# imu_digital.net
KiCad netlist of a schematic drawn in Altium Designer
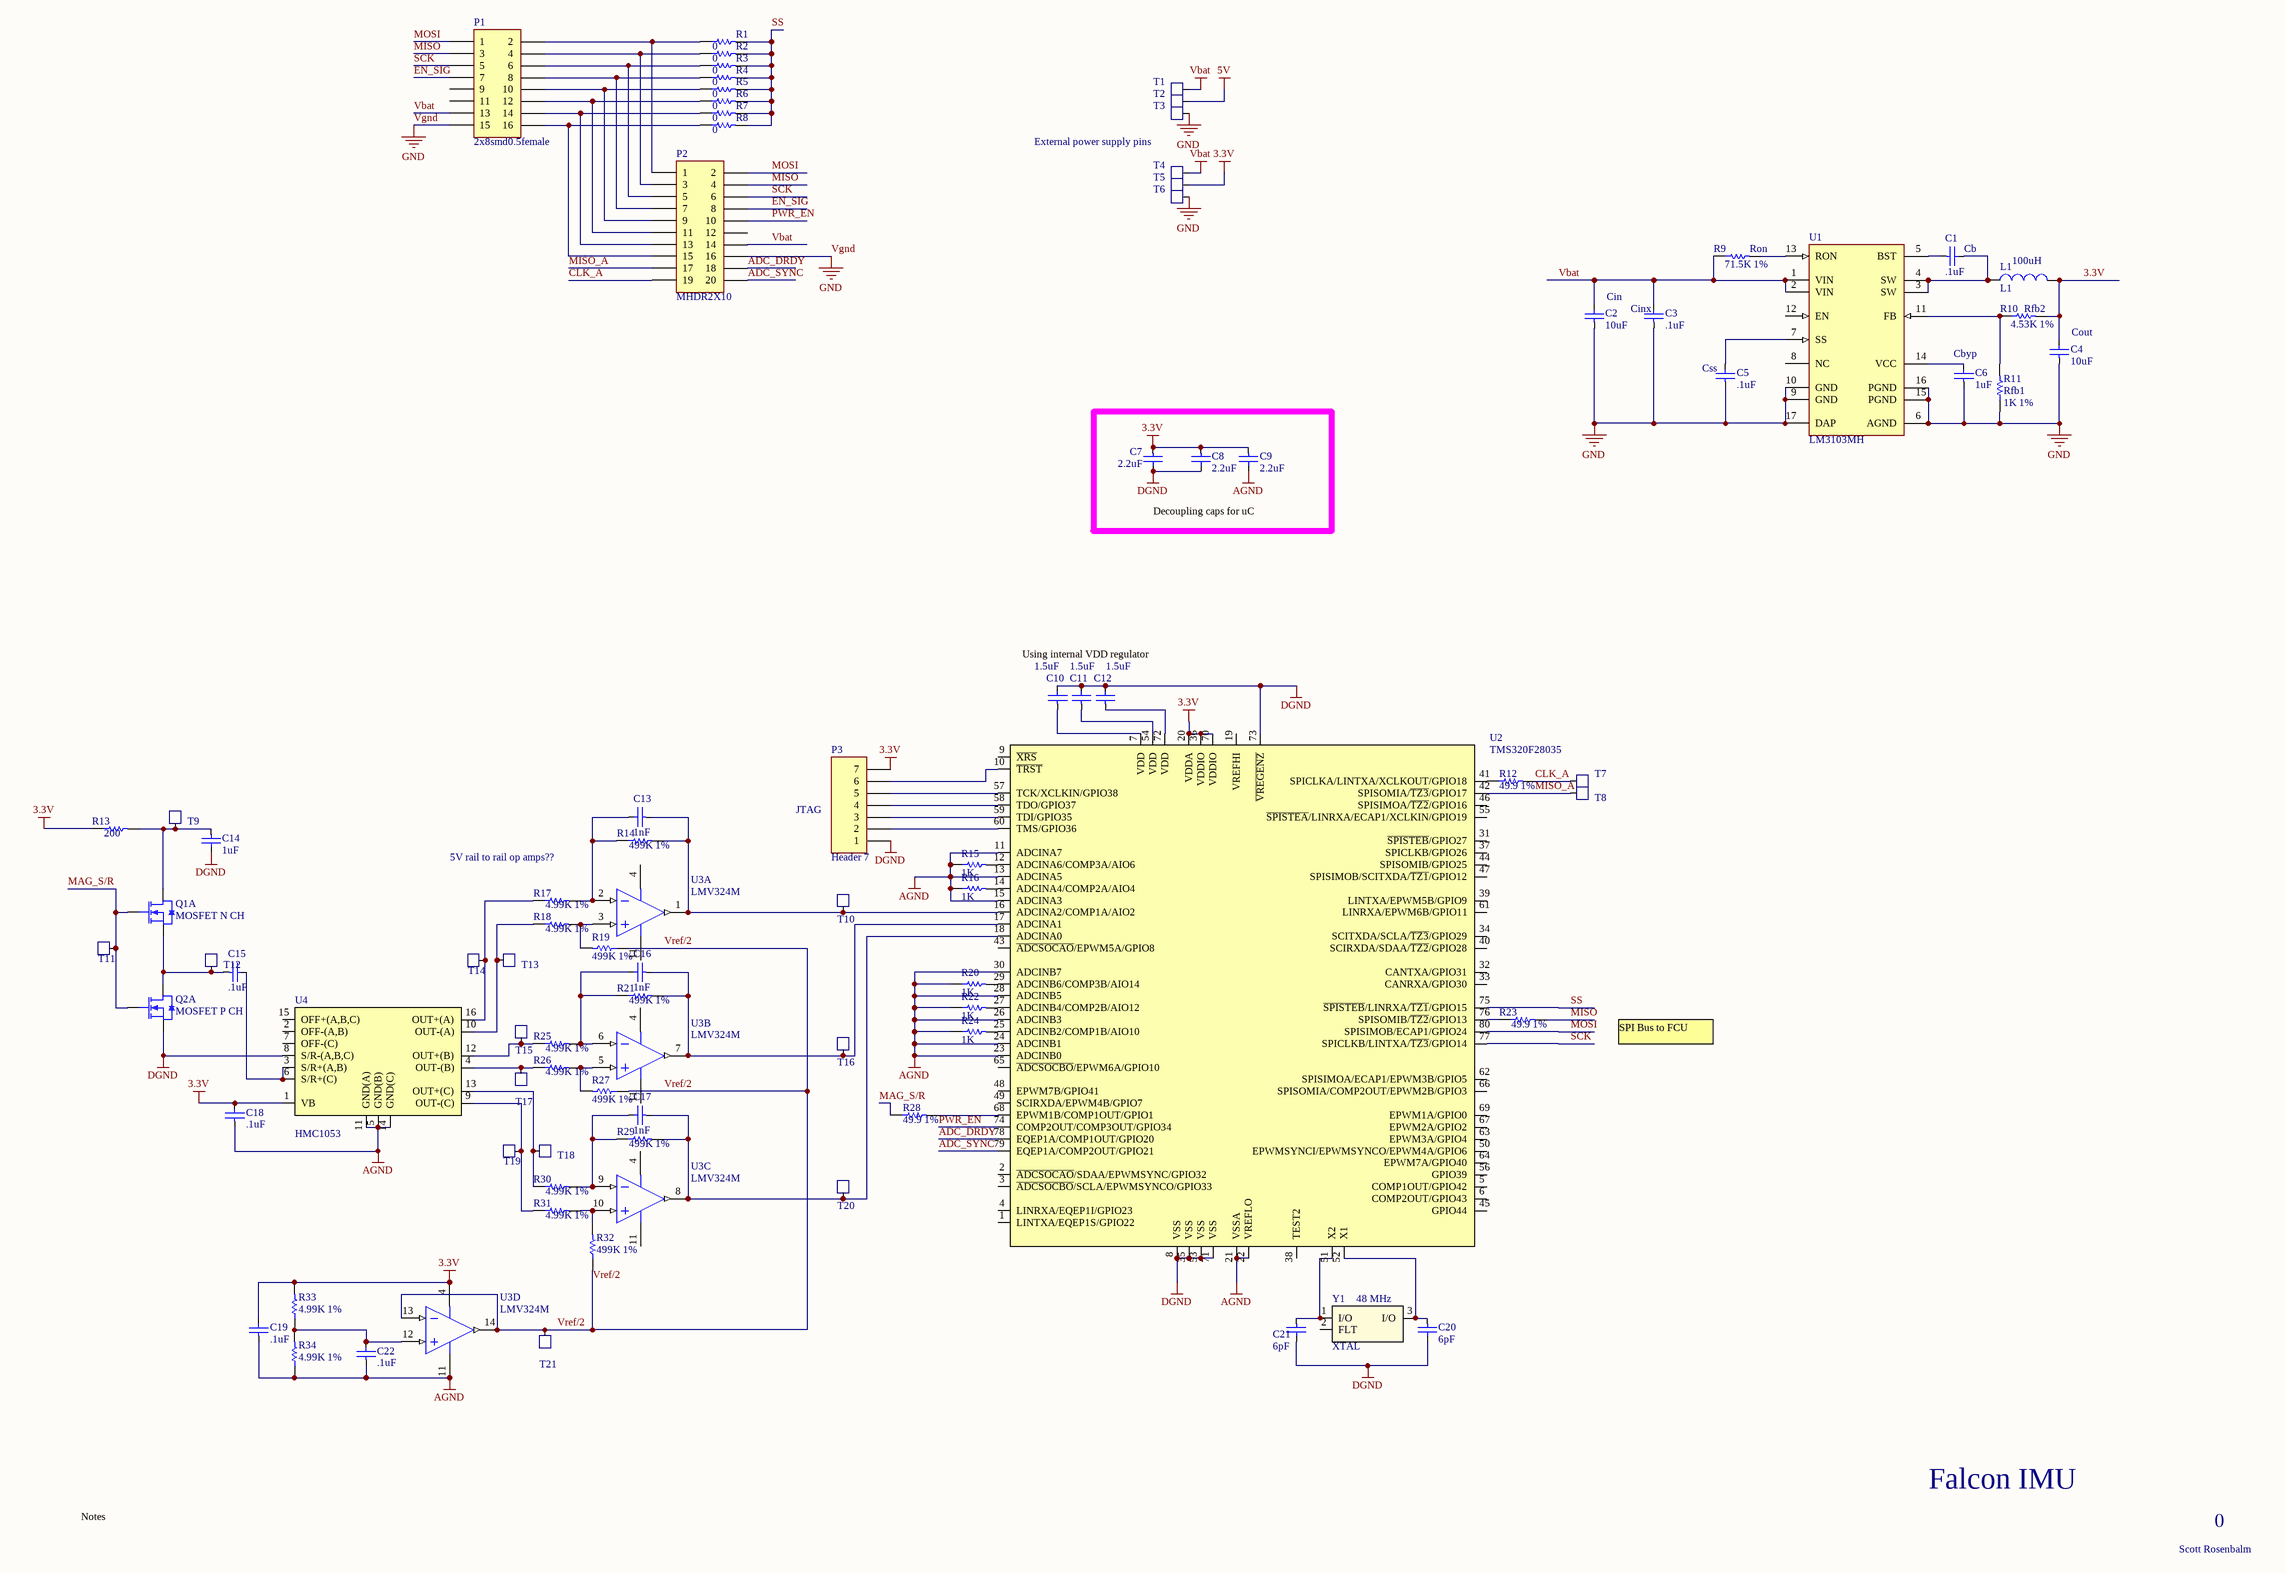
[diagram p0: imu_digital.SchDoc]

(export (version "E")
  (design (tool "Eeschema 10.0.6"))
  (components
    (comp (ref "C1")
      (value "Cb")
      (footprint "0603 (1608)")
      (fields
        (field (name "MANUFACTURER") "Murata")
        (field (name "ALTIUM_VALUE") ".1uF")
        (field (name "PART NO.") "490-1524-1-ND")
      )
      (libsource (lib "SMT Chip") (part "Capacitor"))
    )
    (comp (ref "C2")
      (value "Cin")
      (footprint "1210 (3225)")
      (description "COG Ceramic Cap -> near input to ads1178")
      (fields (field (name "ALTIUM_VALUE") "10uF") (field (name "PART NO.") "810-C3225X7R1E106M"))
      (libsource (lib "SMT Chip") (part "Capacitor"))
    )
    (comp (ref "C3")
      (value "Cinx")
      (footprint "0603 (1608)")
      (fields
        (field (name "MANUFACTURER") "Murata")
        (field (name "ALTIUM_VALUE") ".1uF")
        (field (name "PART NO.") "490-1524-1-ND")
      )
      (libsource (lib "SMT Chip") (part "Capacitor"))
    )
    (comp (ref "C4")
      (value "Cout")
      (footprint "1206 (3216)")
      (description "COG Ceramic Cap -> near input to ads1178")
      (fields (field (name "ALTIUM_VALUE") "10uF") (field (name "PART NO.") "810-C3216X5R1A106M"))
      (libsource (lib "SMT Chip") (part "Capacitor"))
    )
    (comp (ref "C5")
      (value "Css")
      (footprint "0603 (1608)")
      (fields
        (field (name "MANUFACTURER") "Murata")
        (field (name "ALTIUM_VALUE") ".1uF")
        (field (name "PART NO.") "490-1524-1-ND")
      )
      (libsource (lib "SMT Chip") (part "Capacitor"))
    )
    (comp (ref "C6")
      (value "Cbyp")
      (footprint "0603 (1608)")
      (description "COG Ceramic Cap -> near input to ads1178")
      (fields (field (name "ALTIUM_VALUE") "1uF") (field (name "PART NO.") "810-C1608Y5V1A105Z"))
      (libsource (lib "SMT Chip") (part "Capacitor"))
    )
    (comp (ref "C7")
      (value "2.2uF")
      (footprint "0603 (1608)")
      (fields
        (field (name "MANUFACTURER") "TDK")
        (field (name "PART NO.") "445-5167-1-ND")
        (field (name "TOLERANCE") "20%")
      )
      (libsource (lib "SMT Chip") (part "Capacitor"))
    )
    (comp (ref "C8")
      (value "2.2uF")
      (footprint "0603 (1608)")
      (fields
        (field (name "MANUFACTURER") "TDK")
        (field (name "PART NO.") "445-5167-1-ND")
        (field (name "TOLERANCE") "20%")
      )
      (libsource (lib "SMT Chip") (part "Capacitor"))
    )
    (comp (ref "C9")
      (value "2.2uF")
      (footprint "0603 (1608)")
      (fields
        (field (name "MANUFACTURER") "TDK")
        (field (name "PART NO.") "445-5167-1-ND")
        (field (name "TOLERANCE") "20%")
      )
      (libsource (lib "SMT Chip") (part "Capacitor"))
    )
    (comp (ref "C10")
      (value "1.5uF")
      (footprint "0805 (2012)")
      (fields (field (name "MANUFACTURER") "Murata") (field (name "PART NO.") "490-1740-1-ND"))
      (libsource (lib "SMT Chip") (part "Capacitor"))
    )
    (comp (ref "C11")
      (value "1.5uF")
      (footprint "0805 (2012)")
      (fields (field (name "MANUFACTURER") "Murata") (field (name "PART NO.") "490-1740-1-ND"))
      (libsource (lib "SMT Chip") (part "Capacitor"))
    )
    (comp (ref "C12")
      (value "1.5uF")
      (footprint "0805 (2012)")
      (fields (field (name "MANUFACTURER") "Murata") (field (name "PART NO.") "490-1740-1-ND"))
      (libsource (lib "SMT Chip") (part "Capacitor"))
    )
    (comp (ref "C13")
      (value "1nF")
      (footprint "0603 (1608)")
      (fields
        (field (name "MANUFACTURER") "Murata")
        (field (name "PART NO.") "490-1451-1-ND")
        (field (name "TOLERANCE") "5%")
      )
      (libsource (lib "SMT Chip") (part "Capacitor"))
    )
    (comp (ref "C14")
      (value "1uF")
      (footprint "0603 (1608)")
      (fields
        (field (name "MANUFACTURER") "Murata")
        (field (name "PART NO.") "81-GRM188R61E105KA12")
        (field (name "TOLERANCE") "10%")
      )
      (libsource (lib "SMT Chip") (part "Capacitor"))
    )
    (comp (ref "C15")
      (value ".1uF")
      (footprint "0603 (1608)")
      (fields
        (field (name "MANUFACTURER") "Murata")
        (field (name "PART NO.") "490-1524-1-ND")
        (field (name "Comment") "Capacitor")
      )
      (libsource (lib "SMT Chip") (part "Capacitor"))
    )
    (comp (ref "C16")
      (value "1nF")
      (footprint "0603 (1608)")
      (fields
        (field (name "MANUFACTURER") "Murata")
        (field (name "PART NO.") "490-1451-1-ND")
        (field (name "TOLERANCE") "5%")
      )
      (libsource (lib "SMT Chip") (part "Capacitor"))
    )
    (comp (ref "C17")
      (value "1nF")
      (footprint "0603 (1608)")
      (fields
        (field (name "MANUFACTURER") "Murata")
        (field (name "PART NO.") "490-1451-1-ND")
        (field (name "TOLERANCE") "5%")
      )
      (libsource (lib "SMT Chip") (part "Capacitor"))
    )
    (comp (ref "C18")
      (value ".1uF")
      (footprint "0603 (1608)")
      (fields
        (field (name "MANUFACTURER") "Murata")
        (field (name "PART NO.") "490-1524-1-ND")
        (field (name "Comment") "Capacitor")
      )
      (libsource (lib "SMT Chip") (part "Capacitor"))
    )
    (comp (ref "C19")
      (value ".1uF")
      (footprint "0603 (1608)")
      (fields
        (field (name "MANUFACTURER") "Murata")
        (field (name "PART NO.") "490-1524-1-ND")
        (field (name "Comment") "Capacitor")
      )
      (libsource (lib "SMT Chip") (part "Capacitor"))
    )
    (comp (ref "C20")
      (value "6pF")
      (footprint "0603 (1608)")
      (fields
        (field (name "MANUFACTURER") "TDK")
        (field (name "PART NO.") "445-5036-1-ND")
        (field (name "TOLERANCE") ".25pF")
      )
      (libsource (lib "SMT Chip") (part "Capacitor"))
    )
    (comp (ref "C21")
      (value "6pF")
      (footprint "0603 (1608)")
      (fields
        (field (name "MANUFACTURER") "TDK")
        (field (name "PART NO.") "445-5036-1-ND")
        (field (name "TOLERANCE") ".25pF")
      )
      (libsource (lib "SMT Chip") (part "Capacitor"))
    )
    (comp (ref "C22")
      (value ".1uF")
      (footprint "0603 (1608)")
      (fields
        (field (name "MANUFACTURER") "Murata")
        (field (name "PART NO.") "490-1524-1-ND")
        (field (name "Comment") "Capacitor")
      )
      (libsource (lib "SMT Chip") (part "Capacitor"))
    )
    (comp (ref "L1")
      (value "L1")
      (footprint "Inductor Footprint")
      (description "Inductor")
      (fields (field (name "ALTIUM_VALUE") "100uH") (field (name "PART NO.") "SDR0604-101KLCT-ND"))
      (libsource (lib "Miscellaneous Devices") (part "Inductor"))
    )
    (comp (ref "P1")
      (value "2x8smd0.5female")
      (footprint "S9007E-08-ND")
      (fields (field (name "PART NO.") "S9007E-08-ND"))
      (libsource (lib "imu") (part "2x8smd0.5female"))
    )
    (comp (ref "P2")
      (value "MHDR2X10")
      (footprint "S9013E-10-ND")
      (description "Header, 10-Pin, Dual row, Male")
      (fields (field (name "PART NO.") "S9013E-10-ND"))
      (libsource (lib "Miscellaneous Connectors") (part "MHDR2X10"))
    )
    (comp (ref "P3")
      (value "Header 7")
      (footprint "HDR1X7")
      (description "Header, 7-Pin")
      (fields (field (name "PUBLISHER") "Altium Limited"))
      (libsource (lib "Miscellaneous Connectors") (part "Header 7"))
    )
    (comp (ref "Q1")
      (value "MOSFET N CH")
      (footprint "SOT563F")
      (fields (field (name "PART NO.") "SI1035X-T1-E3CT-ND") (field (name "MANUFACTURER") "Vishay Siliconx"))
      (libsource (lib "imu") (part "MOSFETs"))
    )
    (comp (ref "Q2")
      (value "MOSFET P CH")
      (footprint "SOT563F")
      (fields (field (name "PART NO.") "SI1035X-T1-E3CT-ND") (field (name "MANUFACTURER") "Vishay Siliconx"))
      (libsource (lib "imu") (part "MOSFETs"))
    )
    (comp (ref "R1")
      (value "0")
      (footprint "0603 (1608)")
      (description "Resistor")
      (fields (field (name "Comment") "Res1") (field (name "PUBLISHER") "Altium Limited"))
      (libsource (lib "Miscellaneous Devices") (part "Res1"))
    )
    (comp (ref "R2")
      (value "0")
      (footprint "0603 (1608)")
      (description "Resistor")
      (fields (field (name "Comment") "Res1") (field (name "PUBLISHER") "Altium Limited"))
      (libsource (lib "Miscellaneous Devices") (part "Res1"))
    )
    (comp (ref "R3")
      (value "0")
      (footprint "0603 (1608)")
      (description "Resistor")
      (fields (field (name "Comment") "Res1") (field (name "PUBLISHER") "Altium Limited"))
      (libsource (lib "Miscellaneous Devices") (part "Res1"))
    )
    (comp (ref "R4")
      (value "0")
      (footprint "0603 (1608)")
      (description "Resistor")
      (fields (field (name "Comment") "Res1") (field (name "PUBLISHER") "Altium Limited"))
      (libsource (lib "Miscellaneous Devices") (part "Res1"))
    )
    (comp (ref "R5")
      (value "0")
      (footprint "0603 (1608)")
      (description "Resistor")
      (fields (field (name "Comment") "Res1") (field (name "PUBLISHER") "Altium Limited"))
      (libsource (lib "Miscellaneous Devices") (part "Res1"))
    )
    (comp (ref "R6")
      (value "0")
      (footprint "0603 (1608)")
      (description "Resistor")
      (fields (field (name "Comment") "Res1") (field (name "PUBLISHER") "Altium Limited"))
      (libsource (lib "Miscellaneous Devices") (part "Res1"))
    )
    (comp (ref "R7")
      (value "0")
      (footprint "0603 (1608)")
      (description "Resistor")
      (fields (field (name "Comment") "Res1") (field (name "PUBLISHER") "Altium Limited"))
      (libsource (lib "Miscellaneous Devices") (part "Res1"))
    )
    (comp (ref "R8")
      (value "0")
      (footprint "0603 (1608)")
      (description "Resistor")
      (fields (field (name "Comment") "Res1") (field (name "PUBLISHER") "Altium Limited"))
      (libsource (lib "Miscellaneous Devices") (part "Res1"))
    )
    (comp (ref "R9")
      (value "Ron")
      (footprint "0603 (1608)")
      (description "Resistor")
      (fields (field (name "ALTIUM_VALUE") "71.5K 1%") (field (name "PART NO.") "P71.5KHCT-ND"))
      (libsource (lib "Miscellaneous Devices") (part "Res1"))
    )
    (comp (ref "R10")
      (value "Rfb2")
      (footprint "0603 (1608)")
      (description "Resistor")
      (fields (field (name "ALTIUM_VALUE") "4.53K 1%") (field (name "PART NO.") "RMCF0603FT4K53CT-ND"))
      (libsource (lib "Miscellaneous Devices") (part "Res1"))
    )
    (comp (ref "R11")
      (value "Rfb1")
      (footprint "0603 (1608)")
      (description "Resistor")
      (fields (field (name "ALTIUM_VALUE") "1K 1%") (field (name "PART NO.") "P1.00KHCT-ND"))
      (libsource (lib "Miscellaneous Devices") (part "Res1"))
    )
    (comp (ref "R12")
      (value "49.9 1%")
      (footprint "0603 (1608)")
      (description "Resistor")
      (fields (field (name "PART NO.") "P49.9HCT-ND") (field (name "Comment") "931 1%"))
      (libsource (lib "Miscellaneous Devices") (part "Res1"))
    )
    (comp (ref "R13")
      (value "200")
      (footprint "0603 (1608)")
      (description "Resistor")
      (fields (field (name "PART NO.") "P200GCT-ND"))
      (libsource (lib "Miscellaneous Devices") (part "Res1"))
    )
    (comp (ref "R14")
      (value "499K 1%")
      (footprint "0603 (1608)")
      (description "Resistor")
      (fields (field (name "PART NO.") "P499KHCT-ND"))
      (libsource (lib "Miscellaneous Devices") (part "Res1"))
    )
    (comp (ref "R15")
      (value "1K")
      (footprint "0603 (1608)")
      (description "Resistor")
      (fields (field (name "PART NO.") "P1.0KGCT-ND") (field (name "TOLERANCE") "5%"))
      (libsource (lib "Miscellaneous Devices") (part "Res1"))
    )
    (comp (ref "R16")
      (value "1K")
      (footprint "0603 (1608)")
      (description "Resistor")
      (fields (field (name "PART NO.") "P1.0KGCT-ND") (field (name "TOLERANCE") "5%"))
      (libsource (lib "Miscellaneous Devices") (part "Res1"))
    )
    (comp (ref "R17")
      (value "4.99K 1%")
      (footprint "0603 (1608)")
      (description "Resistor")
      (fields (field (name "PART NO.") "P4.99KHCT-ND") (field (name "Comment") "Res1"))
      (libsource (lib "Miscellaneous Devices") (part "Res1"))
    )
    (comp (ref "R18")
      (value "4.99K 1%")
      (footprint "0603 (1608)")
      (description "Resistor")
      (fields (field (name "PART NO.") "P4.99KHCT-ND") (field (name "Comment") "Res1"))
      (libsource (lib "Miscellaneous Devices") (part "Res1"))
    )
    (comp (ref "R19")
      (value "499K 1%")
      (footprint "0603 (1608)")
      (description "Resistor")
      (fields (field (name "PART NO.") "P499KHCT-ND"))
      (libsource (lib "Miscellaneous Devices") (part "Res1"))
    )
    (comp (ref "R20")
      (value "1K")
      (footprint "0603 (1608)")
      (description "Resistor")
      (fields (field (name "PART NO.") "P1.0KGCT-ND") (field (name "TOLERANCE") "5%"))
      (libsource (lib "Miscellaneous Devices") (part "Res1"))
    )
    (comp (ref "R21")
      (value "499K 1%")
      (footprint "0603 (1608)")
      (description "Resistor")
      (fields (field (name "PART NO.") "P499KHCT-ND"))
      (libsource (lib "Miscellaneous Devices") (part "Res1"))
    )
    (comp (ref "R22")
      (value "1K")
      (footprint "0603 (1608)")
      (description "Resistor")
      (fields (field (name "PART NO.") "P1.0KGCT-ND") (field (name "TOLERANCE") "5%"))
      (libsource (lib "Miscellaneous Devices") (part "Res1"))
    )
    (comp (ref "R23")
      (value "49.9 1%")
      (footprint "0603 (1608)")
      (description "Resistor")
      (fields (field (name "PART NO.") "P49.9HCT-ND") (field (name "Comment") "931 1%"))
      (libsource (lib "Miscellaneous Devices") (part "Res1"))
    )
    (comp (ref "R24")
      (value "1K")
      (footprint "0603 (1608)")
      (description "Resistor")
      (fields (field (name "PART NO.") "P1.0KGCT-ND") (field (name "TOLERANCE") "5%"))
      (libsource (lib "Miscellaneous Devices") (part "Res1"))
    )
    (comp (ref "R25")
      (value "4.99K 1%")
      (footprint "0603 (1608)")
      (description "Resistor")
      (fields (field (name "PART NO.") "P4.99KHCT-ND") (field (name "Comment") "Res1"))
      (libsource (lib "Miscellaneous Devices") (part "Res1"))
    )
    (comp (ref "R26")
      (value "4.99K 1%")
      (footprint "0603 (1608)")
      (description "Resistor")
      (fields (field (name "PART NO.") "P4.99KHCT-ND") (field (name "Comment") "Res1"))
      (libsource (lib "Miscellaneous Devices") (part "Res1"))
    )
    (comp (ref "R27")
      (value "499K 1%")
      (footprint "0603 (1608)")
      (description "Resistor")
      (fields (field (name "PART NO.") "P499KHCT-ND"))
      (libsource (lib "Miscellaneous Devices") (part "Res1"))
    )
    (comp (ref "R28")
      (value "49.9 1%")
      (footprint "0603 (1608)")
      (description "Resistor")
      (fields (field (name "PART NO.") "P49.9HCT-ND") (field (name "Comment") "931 1%"))
      (libsource (lib "Miscellaneous Devices") (part "Res1"))
    )
    (comp (ref "R29")
      (value "499K 1%")
      (footprint "0603 (1608)")
      (description "Resistor")
      (fields (field (name "PART NO.") "P499KHCT-ND"))
      (libsource (lib "Miscellaneous Devices") (part "Res1"))
    )
    (comp (ref "R30")
      (value "4.99K 1%")
      (footprint "0603 (1608)")
      (description "Resistor")
      (fields (field (name "PART NO.") "P4.99KHCT-ND") (field (name "Comment") "Res1"))
      (libsource (lib "Miscellaneous Devices") (part "Res1"))
    )
    (comp (ref "R31")
      (value "4.99K 1%")
      (footprint "0603 (1608)")
      (description "Resistor")
      (fields (field (name "PART NO.") "P4.99KHCT-ND") (field (name "Comment") "Res1"))
      (libsource (lib "Miscellaneous Devices") (part "Res1"))
    )
    (comp (ref "R32")
      (value "499K 1%")
      (footprint "0603 (1608)")
      (description "Resistor")
      (fields (field (name "PART NO.") "P499KHCT-ND"))
      (libsource (lib "Miscellaneous Devices") (part "Res1"))
    )
    (comp (ref "R33")
      (value "4.99K 1%")
      (footprint "0603 (1608)")
      (description "Resistor")
      (fields (field (name "PART NO.") "P4.99KHCT-ND") (field (name "Comment") "Res1"))
      (libsource (lib "Miscellaneous Devices") (part "Res1"))
    )
    (comp (ref "R34")
      (value "4.99K 1%")
      (footprint "0603 (1608)")
      (description "Resistor")
      (fields (field (name "PART NO.") "P4.99KHCT-ND") (field (name "Comment") "Res1"))
      (libsource (lib "Miscellaneous Devices") (part "Res1"))
    )
    (comp (ref "T1") (value "TEST_PAD") (footprint "TEST_PAD") (libsource (lib "") (part "TEST_PAD_1")))
    (comp (ref "T2") (value "TEST_PAD") (footprint "TEST_PAD") (libsource (lib "") (part "TEST_PAD_1")))
    (comp (ref "T3") (value "TEST_PAD") (footprint "TEST_PAD") (libsource (lib "") (part "TEST_PAD_1")))
    (comp (ref "T4") (value "TEST_PAD") (footprint "TEST_PAD") (libsource (lib "") (part "TEST_PAD_1")))
    (comp (ref "T5") (value "TEST_PAD") (footprint "TEST_PAD") (libsource (lib "") (part "TEST_PAD_1")))
    (comp (ref "T6") (value "TEST_PAD") (footprint "TEST_PAD") (libsource (lib "") (part "TEST_PAD_1")))
    (comp (ref "T7") (value "~") (footprint "TEST_PAD") (libsource (lib "") (part "TEST_PAD_2")))
    (comp (ref "T8") (value "~") (footprint "TEST_PAD") (libsource (lib "") (part "TEST_PAD_2")))
    (comp (ref "T9") (value "~") (footprint "TEST_PAD") (libsource (lib "imu") (part "TEST_PAD")))
    (comp (ref "T10") (value "~") (footprint "TEST_PAD") (libsource (lib "imu") (part "TEST_PAD")))
    (comp (ref "T11") (value "~") (footprint "TEST_PAD") (libsource (lib "") (part "TEST_PAD_1")))
    (comp (ref "T12") (value "~") (footprint "TEST_PAD") (libsource (lib "imu") (part "TEST_PAD")))
    (comp (ref "T13") (value "~") (footprint "TEST_PAD") (libsource (lib "") (part "TEST_PAD_2")))
    (comp (ref "T14") (value "~") (footprint "TEST_PAD") (libsource (lib "") (part "TEST_PAD_1")))
    (comp (ref "T15") (value "~") (footprint "TEST_PAD") (libsource (lib "imu") (part "TEST_PAD")))
    (comp (ref "T16") (value "~") (footprint "TEST_PAD") (libsource (lib "imu") (part "TEST_PAD")))
    (comp (ref "T17") (value "~") (footprint "TEST_PAD") (libsource (lib "") (part "TEST_PAD_3")))
    (comp (ref "T18") (value "~") (footprint "TEST_PAD") (libsource (lib "") (part "TEST_PAD_2")))
    (comp (ref "T19") (value "~") (footprint "TEST_PAD") (libsource (lib "") (part "TEST_PAD_1")))
    (comp (ref "T20") (value "~") (footprint "TEST_PAD") (libsource (lib "imu") (part "TEST_PAD")))
    (comp (ref "T21") (value "~") (footprint "TEST_PAD") (libsource (lib "") (part "TEST_PAD_3")))
    (comp (ref "U1")
      (value "LM3103MH")
      (footprint "MXA16A_N")
      (description "Synchronous 1MHz 0.75A Step-Down Voltage  Regulator")
      (fields
        (field (name "MANUFACTURER") "National Semiconductor")
        (field (name "DIGIKEYPARTNUMBER") "LM3103MH-ND")
        (field (name "PUBLISHER") "Altium Limited")
      )
      (libsource (lib "NSC Switcher") (part "LM3103MH"))
    )
    (comp (ref "U2")
      (value "TMS320F28035")
      (footprint "TS-PQFP-G80")
      (description "80-pin")
      (fields
        (field (name "MANUFACTURER") "Texas Instruments")
        (field (name "PART NO.") "TMS320F28035PNS-ND")
      )
      (libsource (lib "imu") (part "TMS320F28035 (80-pin)"))
    )
    (comp (ref "U3")
      (value "LMV324M")
      (footprint "M14A_N")
      (description "General Purpose, Low Voltage, Rail-to-Rail Output Operational Amplifiers")
      (fields
        (field (name "MANUFACTURER") "National Semiconductor")
        (field (name "PART NO.") "LMV324MXCT-ND")
        (field (name "DIGIKEYPARTNUMBER") "LMV324MXCT-ND")
        (field (name "PUBLISHER") "Altium Limited")
      )
      (libsource (lib "NSC Amplifier") (part "LMV324M"))
    )
    (comp (ref "U4") (value "HMC1053") (footprint "LCC-16") (libsource (lib "imu") (part "HMC1053")))
    (comp (ref "Y1")
      (value "XTAL")
      (footprint "Murata XTAL")
      (fields (field (name "PART NO.") "490-5588-1-ND") (field (name "FREQUENCY") "48 MHz"))
      (libsource (lib "imu") (part "XTAL"))
    )
  )
  (nets
    (net (code "1") (name "/ADC_DRDY") (class "Default")
      (node (ref "P2") (pin "18") (pinfunction "18_18") (pintype "passive"))
      (node (ref "U2") (pin "78") (pinfunction "EQEP1A/COMP1OUT/GPIO20_78") (pintype "passive"))
    )
    (net (code "2") (name "/ADC_SYNC") (class "Default")
      (node (ref "P2") (pin "20") (pinfunction "20_20") (pintype "passive"))
      (node (ref "U2") (pin "79") (pinfunction "EQEP1A/COMP2OUT/GPIO21_79") (pintype "passive"))
    )
    (net (code "3") (name "/CLK_A") (class "Default")
      (node (ref "P2") (pin "19") (pinfunction "19_19") (pintype "passive"))
      (node (ref "R12") (pin "2") (pinfunction "2_2") (pintype "passive"))
      (node (ref "T7") (pin "0") (pintype "passive"))
    )
    (net (code "4") (name "/EN_SIG") (class "Default")
      (node (ref "P1") (pin "7") (pinfunction "7_7") (pintype "passive"))
      (node (ref "P2") (pin "8") (pinfunction "8_8") (pintype "passive"))
    )
    (net (code "5") (name "/MAG_S{slash}R") (class "Default")
      (node (ref "Q1") (pin "2") (pinfunction "G1_2") (pintype "passive"))
      (node (ref "Q2") (pin "2") (pinfunction "G1_2") (pintype "passive"))
      (node (ref "R28") (pin "1") (pinfunction "1_1") (pintype "passive"))
      (node (ref "T11") (pin "0") (pintype "passive"))
    )
    (net (code "6") (name "/MISO") (class "Default")
      (node (ref "P1") (pin "3") (pinfunction "3_3") (pintype "passive"))
      (node (ref "P2") (pin "4") (pinfunction "4_4") (pintype "passive"))
      (node (ref "R23") (pin "2") (pinfunction "2_2") (pintype "passive"))
    )
    (net (code "7") (name "/MISO_A") (class "Default")
      (node (ref "P2") (pin "17") (pinfunction "17_17") (pintype "passive"))
      (node (ref "T8") (pin "0") (pintype "passive"))
      (node (ref "U2") (pin "42") (pinfunction "SPISOMIA/~{TZ3}/GPIO17_42") (pintype "passive"))
    )
    (net (code "8") (name "/MOSI") (class "Default")
      (node (ref "P1") (pin "1") (pinfunction "1_1") (pintype "passive"))
      (node (ref "P2") (pin "2") (pinfunction "2_2") (pintype "passive"))
      (node (ref "U2") (pin "80") (pinfunction "SPISIMOB/ECAP1/GPIO24_80") (pintype "passive"))
    )
    (net (code "9") (name "/PWR_EN") (class "Default")
      (node (ref "P2") (pin "10") (pinfunction "10_10") (pintype "passive"))
      (node (ref "U2") (pin "74") (pinfunction "COMP2OUT/COMP3OUT/GPIO34_74") (pintype "passive"))
    )
    (net (code "10") (name "/SCK") (class "Default")
      (node (ref "P1") (pin "5") (pinfunction "5_5") (pintype "passive"))
      (node (ref "P2") (pin "6") (pinfunction "6_6") (pintype "passive"))
      (node (ref "U2") (pin "77") (pinfunction "SPICLKB/LINTXA/~{TZ3}/GPIO14_77") (pintype "passive"))
    )
    (net (code "11") (name "/SS") (class "Default")
      (node (ref "R1") (pin "2") (pinfunction "2_2") (pintype "passive"))
      (node (ref "R2") (pin "2") (pinfunction "2_2") (pintype "passive"))
      (node (ref "R3") (pin "2") (pinfunction "2_2") (pintype "passive"))
      (node (ref "R4") (pin "2") (pinfunction "2_2") (pintype "passive"))
      (node (ref "R5") (pin "2") (pinfunction "2_2") (pintype "passive"))
      (node (ref "R6") (pin "2") (pinfunction "2_2") (pintype "passive"))
      (node (ref "R7") (pin "2") (pinfunction "2_2") (pintype "passive"))
      (node (ref "R8") (pin "2") (pinfunction "2_2") (pintype "passive"))
      (node (ref "U2") (pin "75") (pinfunction "~{SPISTEB}/LINRXA/~{TZ1}/GPIO15_75") (pintype "passive"))
    )
    (net (code "12") (name "/Vref{slash}2") (class "Default")
      (node (ref "R19") (pin "1") (pinfunction "1_1") (pintype "passive"))
      (node (ref "R27") (pin "1") (pinfunction "1_1") (pintype "passive"))
      (node (ref "R32") (pin "1") (pinfunction "1_1") (pintype "passive"))
      (node (ref "T21") (pin "0") (pintype "passive"))
      (node (ref "U3") (pin "13") (pinfunction "IND-_13") (pintype "input"))
      (node (ref "U3") (pin "14") (pinfunction "OUTD_14") (pintype "output"))
    )
    (net (code "13") (name "3.3V") (class "Default")
      (node (ref "C18") (pin "1") (pinfunction "1_1") (pintype "passive"))
      (node (ref "C19") (pin "1") (pinfunction "1_1") (pintype "passive"))
      (node (ref "C4") (pin "1") (pinfunction "1_1") (pintype "passive"))
      (node (ref "C7") (pin "2") (pinfunction "2_2") (pintype "passive"))
      (node (ref "C8") (pin "2") (pinfunction "2_2") (pintype "passive"))
      (node (ref "C9") (pin "2") (pinfunction "2_2") (pintype "passive"))
      (node (ref "L1") (pin "2") (pinfunction "2_2") (pintype "passive"))
      (node (ref "P3") (pin "7") (pinfunction "7_7") (pintype "passive"))
      (node (ref "R10") (pin "2") (pinfunction "2_2") (pintype "passive"))
      (node (ref "R13") (pin "1") (pinfunction "1_1") (pintype "passive"))
      (node (ref "R33") (pin "2") (pinfunction "2_2") (pintype "passive"))
      (node (ref "T5") (pin "0") (pintype "passive"))
      (node (ref "U2") (pin "20") (pinfunction "VDDA_20") (pintype "passive"))
      (node (ref "U2") (pin "36") (pinfunction "VDDIO_36") (pintype "passive"))
      (node (ref "U2") (pin "70") (pinfunction "VDDIO_70") (pintype "passive"))
      (node (ref "U3") (pin "4") (pinfunction "V+_4") (pintype "power_in"))
      (node (ref "U4") (pin "1") (pinfunction "VB_1") (pintype "passive"))
    )
    (net (code "14") (name "5V") (class "Default") (node (ref "T2") (pin "0") (pintype "passive")))
    (net (code "15") (name "AGND") (class "Default")
      (node (ref "C18") (pin "2") (pinfunction "2_2") (pintype "passive"))
      (node (ref "C19") (pin "2") (pinfunction "2_2") (pintype "passive"))
      (node (ref "C22") (pin "2") (pinfunction "2_2") (pintype "passive"))
      (node (ref "C9") (pin "1") (pinfunction "1_1") (pintype "passive"))
      (node (ref "R15") (pin "1") (pinfunction "1_1") (pintype "passive"))
      (node (ref "R16") (pin "1") (pinfunction "1_1") (pintype "passive"))
      (node (ref "R20") (pin "1") (pinfunction "1_1") (pintype "passive"))
      (node (ref "R22") (pin "1") (pinfunction "1_1") (pintype "passive"))
      (node (ref "R24") (pin "1") (pinfunction "1_1") (pintype "passive"))
      (node (ref "R34") (pin "1") (pinfunction "1_1") (pintype "passive"))
      (node (ref "U2") (pin "11") (pinfunction "ADCINA7_11") (pintype "passive"))
      (node (ref "U2") (pin "13") (pinfunction "ADCINA5_13") (pintype "passive"))
      (node (ref "U2") (pin "15") (pinfunction "ADCINA3_15") (pintype "passive"))
      (node (ref "U2") (pin "21") (pinfunction "VSSA_21") (pintype "passive"))
      (node (ref "U2") (pin "22") (pinfunction "VREFLO_22") (pintype "passive"))
      (node (ref "U2") (pin "23") (pinfunction "ADCINB0_23") (pintype "passive"))
      (node (ref "U2") (pin "24") (pinfunction "ADCINB1_24") (pintype "passive"))
      (node (ref "U2") (pin "26") (pinfunction "ADCINB3_26") (pintype "passive"))
      (node (ref "U2") (pin "28") (pinfunction "ADCINB5_28") (pintype "passive"))
      (node (ref "U2") (pin "30") (pinfunction "ADCINB7_30") (pintype "passive"))
      (node (ref "U3") (pin "11") (pinfunction "V-_11") (pintype "power_in"))
      (node (ref "U4") (pin "11") (pinfunction "GND(A)_11") (pintype "passive"))
      (node (ref "U4") (pin "14") (pinfunction "GND(C)_14") (pintype "passive"))
      (node (ref "U4") (pin "5") (pinfunction "GND(B)_5") (pintype "passive"))
    )
    (net (code "16") (name "DGND") (class "Default")
      (node (ref "C10") (pin "1") (pinfunction "1_1") (pintype "passive"))
      (node (ref "C11") (pin "1") (pinfunction "1_1") (pintype "passive"))
      (node (ref "C12") (pin "1") (pinfunction "1_1") (pintype "passive"))
      (node (ref "C14") (pin "1") (pinfunction "1_1") (pintype "passive"))
      (node (ref "C20") (pin "1") (pinfunction "1_1") (pintype "passive"))
      (node (ref "C21") (pin "1") (pinfunction "1_1") (pintype "passive"))
      (node (ref "C7") (pin "1") (pinfunction "1_1") (pintype "passive"))
      (node (ref "C8") (pin "1") (pinfunction "1_1") (pintype "passive"))
      (node (ref "P3") (pin "1") (pinfunction "1_1") (pintype "passive"))
      (node (ref "Q2") (pin "1") (pinfunction "S1_1") (pintype "passive"))
      (node (ref "U2") (pin "35") (pinfunction "VSS_35") (pintype "passive"))
      (node (ref "U2") (pin "53") (pinfunction "VSS_53") (pintype "passive"))
      (node (ref "U2") (pin "71") (pinfunction "VSS_71") (pintype "passive"))
      (node (ref "U2") (pin "73") (pinfunction "~{VREGENZ}_73") (pintype "passive"))
      (node (ref "U2") (pin "8") (pinfunction "VSS_8") (pintype "passive"))
      (node (ref "U4") (pin "8") (pinfunction "S/R-(A,B,C)_8") (pintype "passive"))
    )
    (net (code "17") (name "GND") (class "Default")
      (node (ref "C2") (pin "2") (pinfunction "2_2") (pintype "passive"))
      (node (ref "C3") (pin "2") (pinfunction "2_2") (pintype "passive"))
      (node (ref "C4") (pin "2") (pinfunction "2_2") (pintype "passive"))
      (node (ref "C5") (pin "2") (pinfunction "2_2") (pintype "passive"))
      (node (ref "C6") (pin "2") (pinfunction "2_2") (pintype "passive"))
      (node (ref "P1") (pin "15") (pinfunction "15_15") (pintype "passive"))
      (node (ref "P2") (pin "16") (pinfunction "16_16") (pintype "passive"))
      (node (ref "R11") (pin "1") (pinfunction "1_1") (pintype "passive"))
      (node (ref "T3") (pin "0") (pintype "passive"))
      (node (ref "T6") (pin "0") (pintype "passive"))
      (node (ref "U1") (pin "10") (pinfunction "GND_10") (pintype "power_in"))
      (node (ref "U1") (pin "15") (pinfunction "PGND_15") (pintype "power_in"))
      (node (ref "U1") (pin "16") (pinfunction "PGND_16") (pintype "power_in"))
      (node (ref "U1") (pin "17") (pinfunction "DAP_17") (pintype "power_in"))
      (node (ref "U1") (pin "6") (pinfunction "AGND_6") (pintype "power_in"))
      (node (ref "U1") (pin "9") (pinfunction "GND_9") (pintype "power_in"))
    )
    (net (code "18") (name "Net-(C1-Pad1)") (class "Default")
      (node (ref "C1") (pin "1") (pinfunction "1_1") (pintype "passive"))
      (node (ref "L1") (pin "1") (pinfunction "1_1") (pintype "passive"))
      (node (ref "U1") (pin "3") (pinfunction "SW_3") (pintype "power_in"))
      (node (ref "U1") (pin "4") (pinfunction "SW_4") (pintype "power_in"))
    )
    (net (code "19") (name "Net-(C10-Pad2)") (class "Default")
      (node (ref "C10") (pin "2") (pinfunction "2_2") (pintype "passive"))
      (node (ref "U2") (pin "7") (pinfunction "VDD_7") (pintype "passive"))
    )
    (net (code "20") (name "Net-(C11-Pad2)") (class "Default")
      (node (ref "C11") (pin "2") (pinfunction "2_2") (pintype "passive"))
      (node (ref "U2") (pin "54") (pinfunction "VDD_54") (pintype "passive"))
    )
    (net (code "21") (name "Net-(C12-Pad2)") (class "Default")
      (node (ref "C12") (pin "2") (pinfunction "2_2") (pintype "passive"))
      (node (ref "U2") (pin "72") (pinfunction "VDD_72") (pintype "passive"))
    )
    (net (code "22") (name "Net-(P1-Pad2)") (class "Default")
      (node (ref "P1") (pin "2") (pinfunction "2_2") (pintype "passive"))
      (node (ref "P2") (pin "1") (pinfunction "1_1") (pintype "passive"))
      (node (ref "R1") (pin "1") (pinfunction "1_1") (pintype "passive"))
    )
    (net (code "23") (name "Net-(P1-Pad4)") (class "Default")
      (node (ref "P1") (pin "4") (pinfunction "4_4") (pintype "passive"))
      (node (ref "P2") (pin "3") (pinfunction "3_3") (pintype "passive"))
      (node (ref "R2") (pin "1") (pinfunction "1_1") (pintype "passive"))
    )
    (net (code "24") (name "Net-(P1-Pad6)") (class "Default")
      (node (ref "P1") (pin "6") (pinfunction "6_6") (pintype "passive"))
      (node (ref "P2") (pin "5") (pinfunction "5_5") (pintype "passive"))
      (node (ref "R3") (pin "1") (pinfunction "1_1") (pintype "passive"))
    )
    (net (code "25") (name "Net-(P1-Pad8)") (class "Default")
      (node (ref "P1") (pin "8") (pinfunction "8_8") (pintype "passive"))
      (node (ref "P2") (pin "7") (pinfunction "7_7") (pintype "passive"))
      (node (ref "R4") (pin "1") (pinfunction "1_1") (pintype "passive"))
    )
    (net (code "26") (name "Net-(P1-Pad10)") (class "Default")
      (node (ref "P1") (pin "10") (pinfunction "10_10") (pintype "passive"))
      (node (ref "P2") (pin "9") (pinfunction "9_9") (pintype "passive"))
      (node (ref "R5") (pin "1") (pinfunction "1_1") (pintype "passive"))
    )
    (net (code "27") (name "Net-(P1-Pad12)") (class "Default")
      (node (ref "P1") (pin "12") (pinfunction "12_12") (pintype "passive"))
      (node (ref "P2") (pin "11") (pinfunction "11_11") (pintype "passive"))
      (node (ref "R6") (pin "1") (pinfunction "1_1") (pintype "passive"))
    )
    (net (code "28") (name "Net-(P1-Pad14)") (class "Default")
      (node (ref "P1") (pin "14") (pinfunction "14_14") (pintype "passive"))
      (node (ref "P2") (pin "13") (pinfunction "13_13") (pintype "passive"))
      (node (ref "R7") (pin "1") (pinfunction "1_1") (pintype "passive"))
    )
    (net (code "29") (name "Net-(P1-Pad16)") (class "Default")
      (node (ref "P1") (pin "16") (pinfunction "16_16") (pintype "passive"))
      (node (ref "P2") (pin "15") (pinfunction "15_15") (pintype "passive"))
      (node (ref "R8") (pin "1") (pinfunction "1_1") (pintype "passive"))
    )
    (net (code "30") (name "Net-(Q1A-D1)") (class "Default")
      (node (ref "C14") (pin "2") (pinfunction "2_2") (pintype "passive"))
      (node (ref "Q1") (pin "6") (pinfunction "D1_6") (pintype "passive"))
      (node (ref "R13") (pin "2") (pinfunction "2_2") (pintype "passive"))
      (node (ref "T9") (pin "0") (pintype "passive"))
    )
    (net (code "31") (name "Net-(Q1A-S1)") (class "Default")
      (node (ref "C15") (pin "2") (pinfunction "2_2") (pintype "passive"))
      (node (ref "Q1") (pin "1") (pinfunction "S1_1") (pintype "passive"))
      (node (ref "Q2") (pin "6") (pinfunction "D1_6") (pintype "passive"))
      (node (ref "T12") (pin "0") (pintype "passive"))
    )
    (net (code "32") (name "Net-(U1-BST)") (class "Default")
      (node (ref "C1") (pin "2") (pinfunction "2_2") (pintype "passive"))
      (node (ref "U1") (pin "5") (pinfunction "BST_5") (pintype "passive"))
    )
    (net (code "33") (name "Net-(U1-FB)") (class "Default")
      (node (ref "R10") (pin "1") (pinfunction "1_1") (pintype "passive"))
      (node (ref "R11") (pin "2") (pinfunction "2_2") (pintype "passive"))
      (node (ref "U1") (pin "11") (pinfunction "FB_11") (pintype "input"))
    )
    (net (code "34") (name "Net-(U1-RON)") (class "Default")
      (node (ref "R9") (pin "2") (pinfunction "2_2") (pintype "passive"))
      (node (ref "U1") (pin "13") (pinfunction "RON_13") (pintype "input"))
    )
    (net (code "35") (name "Net-(U1-SS)") (class "Default")
      (node (ref "C5") (pin "1") (pinfunction "1_1") (pintype "passive"))
      (node (ref "U1") (pin "7") (pinfunction "SS_7") (pintype "input"))
    )
    (net (code "36") (name "Net-(U1-VCC)") (class "Default")
      (node (ref "C6") (pin "1") (pinfunction "1_1") (pintype "passive"))
      (node (ref "U1") (pin "14") (pinfunction "VCC_14") (pintype "power_in"))
    )
    (net (code "37") (name "Net-(U2-ADCINA0)") (class "Default")
      (node (ref "C17") (pin "2") (pinfunction "2_2") (pintype "passive"))
      (node (ref "R29") (pin "2") (pinfunction "2_2") (pintype "passive"))
      (node (ref "T20") (pin "0") (pintype "passive"))
      (node (ref "U2") (pin "18") (pinfunction "ADCINA0_18") (pintype "passive"))
      (node (ref "U3") (pin "8") (pinfunction "OUTC_8") (pintype "output"))
    )
    (net (code "38") (name "Net-(U2-ADCINA1)") (class "Default")
      (node (ref "C16") (pin "2") (pinfunction "2_2") (pintype "passive"))
      (node (ref "R21") (pin "2") (pinfunction "2_2") (pintype "passive"))
      (node (ref "T16") (pin "0") (pintype "passive"))
      (node (ref "U2") (pin "17") (pinfunction "ADCINA1_17") (pintype "passive"))
      (node (ref "U3") (pin "7") (pinfunction "OUTB_7") (pintype "output"))
    )
    (net (code "39") (name "Net-(U2-ADCINA2{slash}COMP1A{slash}AIO2)") (class "Default")
      (node (ref "C13") (pin "2") (pinfunction "2_2") (pintype "passive"))
      (node (ref "R14") (pin "2") (pinfunction "2_2") (pintype "passive"))
      (node (ref "T10") (pin "0") (pintype "passive"))
      (node (ref "U2") (pin "16") (pinfunction "ADCINA2/COMP1A/AIO2_16") (pintype "passive"))
      (node (ref "U3") (pin "1") (pinfunction "OUTA_1") (pintype "output"))
    )
    (net (code "40") (name "Net-(U2-ADCINA4{slash}COMP2A{slash}AIO4)") (class "Default")
      (node (ref "R16") (pin "2") (pinfunction "2_2") (pintype "passive"))
      (node (ref "U2") (pin "14") (pinfunction "ADCINA4/COMP2A/AIO4_14") (pintype "passive"))
    )
    (net (code "41") (name "Net-(U2-ADCINA6{slash}COMP3A{slash}AIO6)") (class "Default")
      (node (ref "R15") (pin "2") (pinfunction "2_2") (pintype "passive"))
      (node (ref "U2") (pin "12") (pinfunction "ADCINA6/COMP3A/AIO6_12") (pintype "passive"))
    )
    (net (code "42") (name "Net-(U2-ADCINB2{slash}COMP1B{slash}AIO10)") (class "Default")
      (node (ref "R24") (pin "2") (pinfunction "2_2") (pintype "passive"))
      (node (ref "U2") (pin "25") (pinfunction "ADCINB2/COMP1B/AIO10_25") (pintype "passive"))
    )
    (net (code "43") (name "Net-(U2-ADCINB4{slash}COMP2B{slash}AIO12)") (class "Default")
      (node (ref "R22") (pin "2") (pinfunction "2_2") (pintype "passive"))
      (node (ref "U2") (pin "27") (pinfunction "ADCINB4/COMP2B/AIO12_27") (pintype "passive"))
    )
    (net (code "44") (name "Net-(U2-ADCINB6{slash}COMP3B{slash}AIO14)") (class "Default")
      (node (ref "R20") (pin "2") (pinfunction "2_2") (pintype "passive"))
      (node (ref "U2") (pin "29") (pinfunction "ADCINB6/COMP3B/AIO14_29") (pintype "passive"))
    )
    (net (code "45") (name "Net-(U2-EPWM1B{slash}COMP1OUT{slash}GPIO1)") (class "Default")
      (node (ref "R28") (pin "2") (pinfunction "2_2") (pintype "passive"))
      (node (ref "U2") (pin "68") (pinfunction "EPWM1B/COMP1OUT/GPIO1_68") (pintype "passive"))
    )
    (net (code "46") (name "Net-(U2-SPICLKA{slash}LINTXA{slash}XCLKOUT{slash}GPIO18)") (class "Default")
      (node (ref "R12") (pin "1") (pinfunction "1_1") (pintype "passive"))
      (node (ref "U2") (pin "41") (pinfunction "SPICLKA/LINTXA/XCLKOUT/GPIO18_41") (pintype "passive"))
    )
    (net (code "47") (name "Net-(U2-SPISOMIB{slash}~{TZ2}{slash}GPIO13)") (class "Default")
      (node (ref "R23") (pin "1") (pinfunction "1_1") (pintype "passive"))
      (node (ref "U2") (pin "76") (pinfunction "SPISOMIB/~{TZ2}/GPIO13_76") (pintype "passive"))
    )
    (net (code "48") (name "Net-(U2-TCK{slash}XCLKIN{slash}GPIO38)") (class "Default")
      (node (ref "P3") (pin "5") (pinfunction "5_5") (pintype "passive"))
      (node (ref "U2") (pin "57") (pinfunction "TCK/XCLKIN/GPIO38_57") (pintype "passive"))
    )
    (net (code "49") (name "Net-(U2-TDI{slash}GPIO35)") (class "Default")
      (node (ref "P3") (pin "3") (pinfunction "3_3") (pintype "passive"))
      (node (ref "U2") (pin "59") (pinfunction "TDI/GPIO35_59") (pintype "passive"))
    )
    (net (code "50") (name "Net-(U2-TDO{slash}GPIO37)") (class "Default")
      (node (ref "P3") (pin "4") (pinfunction "4_4") (pintype "passive"))
      (node (ref "U2") (pin "58") (pinfunction "TDO/GPIO37_58") (pintype "passive"))
    )
    (net (code "51") (name "Net-(U2-TMS{slash}GPIO36)") (class "Default")
      (node (ref "P3") (pin "2") (pinfunction "2_2") (pintype "passive"))
      (node (ref "U2") (pin "60") (pinfunction "TMS/GPIO36_60") (pintype "passive"))
    )
    (net (code "52") (name "Net-(U2-X1)") (class "Default")
      (node (ref "C20") (pin "2") (pinfunction "2_2") (pintype "passive"))
      (node (ref "U2") (pin "52") (pinfunction "X1_52") (pintype "passive"))
      (node (ref "Y1") (pin "3") (pinfunction "I/O_3") (pintype "passive"))
    )
    (net (code "53") (name "Net-(U2-X2)") (class "Default")
      (node (ref "C21") (pin "2") (pinfunction "2_2") (pintype "passive"))
      (node (ref "U2") (pin "51") (pinfunction "X2_51") (pintype "passive"))
      (node (ref "Y1") (pin "1") (pinfunction "I/O_1") (pintype "passive"))
    )
    (net (code "54") (name "Net-(U2-~{TRST})") (class "Default")
      (node (ref "P3") (pin "6") (pinfunction "6_6") (pintype "passive"))
      (node (ref "U2") (pin "10") (pinfunction "~{TRST}_10") (pintype "passive"))
    )
    (net (code "55") (name "Net-(U3A-INA+)") (class "Default")
      (node (ref "R18") (pin "2") (pinfunction "2_2") (pintype "passive"))
      (node (ref "R19") (pin "2") (pinfunction "2_2") (pintype "passive"))
      (node (ref "U3") (pin "3") (pinfunction "INA+_3") (pintype "input"))
    )
    (net (code "56") (name "Net-(U3A-INA-)") (class "Default")
      (node (ref "C13") (pin "1") (pinfunction "1_1") (pintype "passive"))
      (node (ref "R14") (pin "1") (pinfunction "1_1") (pintype "passive"))
      (node (ref "R17") (pin "2") (pinfunction "2_2") (pintype "passive"))
      (node (ref "U3") (pin "2") (pinfunction "INA-_2") (pintype "input"))
    )
    (net (code "57") (name "Net-(U3B-INB+)") (class "Default")
      (node (ref "R26") (pin "2") (pinfunction "2_2") (pintype "passive"))
      (node (ref "R27") (pin "2") (pinfunction "2_2") (pintype "passive"))
      (node (ref "U3") (pin "5") (pinfunction "INB+_5") (pintype "input"))
    )
    (net (code "58") (name "Net-(U3B-INB-)") (class "Default")
      (node (ref "C16") (pin "1") (pinfunction "1_1") (pintype "passive"))
      (node (ref "R21") (pin "1") (pinfunction "1_1") (pintype "passive"))
      (node (ref "R25") (pin "2") (pinfunction "2_2") (pintype "passive"))
      (node (ref "U3") (pin "6") (pinfunction "INB-_6") (pintype "input"))
    )
    (net (code "59") (name "Net-(U3C-INC+)") (class "Default")
      (node (ref "R31") (pin "2") (pinfunction "2_2") (pintype "passive"))
      (node (ref "R32") (pin "2") (pinfunction "2_2") (pintype "passive"))
      (node (ref "U3") (pin "10") (pinfunction "INC+_10") (pintype "input"))
    )
    (net (code "60") (name "Net-(U3C-INC-)") (class "Default")
      (node (ref "C17") (pin "1") (pinfunction "1_1") (pintype "passive"))
      (node (ref "R29") (pin "1") (pinfunction "1_1") (pintype "passive"))
      (node (ref "R30") (pin "2") (pinfunction "2_2") (pintype "passive"))
      (node (ref "U3") (pin "9") (pinfunction "INC-_9") (pintype "input"))
    )
    (net (code "61") (name "Net-(U3D-IND+)") (class "Default")
      (node (ref "C22") (pin "1") (pinfunction "1_1") (pintype "passive"))
      (node (ref "R33") (pin "1") (pinfunction "1_1") (pintype "passive"))
      (node (ref "R34") (pin "2") (pinfunction "2_2") (pintype "passive"))
      (node (ref "U3") (pin "12") (pinfunction "IND+_12") (pintype "input"))
    )
    (net (code "62") (name "Net-(U4-OUT+(A))") (class "Default")
      (node (ref "R17") (pin "1") (pinfunction "1_1") (pintype "passive"))
      (node (ref "T14") (pin "0") (pintype "passive"))
      (node (ref "U4") (pin "16") (pinfunction "OUT+(A)_16") (pintype "passive"))
    )
    (net (code "63") (name "Net-(U4-OUT+(B))") (class "Default")
      (node (ref "R25") (pin "1") (pinfunction "1_1") (pintype "passive"))
      (node (ref "T15") (pin "0") (pintype "passive"))
      (node (ref "U4") (pin "12") (pinfunction "OUT+(B)_12") (pintype "passive"))
    )
    (net (code "64") (name "Net-(U4-OUT+(C))") (class "Default")
      (node (ref "R30") (pin "1") (pinfunction "1_1") (pintype "passive"))
      (node (ref "T18") (pin "0") (pintype "passive"))
      (node (ref "U4") (pin "13") (pinfunction "OUT+(C)_13") (pintype "passive"))
    )
    (net (code "65") (name "Net-(U4-OUT-(A))") (class "Default")
      (node (ref "R18") (pin "1") (pinfunction "1_1") (pintype "passive"))
      (node (ref "T13") (pin "0") (pintype "passive"))
      (node (ref "U4") (pin "10") (pinfunction "OUT-(A)_10") (pintype "passive"))
    )
    (net (code "66") (name "Net-(U4-OUT-(B))") (class "Default")
      (node (ref "R26") (pin "1") (pinfunction "1_1") (pintype "passive"))
      (node (ref "T17") (pin "0") (pintype "passive"))
      (node (ref "U4") (pin "4") (pinfunction "OUT-(B)_4") (pintype "passive"))
    )
    (net (code "67") (name "Net-(U4-OUT-(C))") (class "Default")
      (node (ref "R31") (pin "1") (pinfunction "1_1") (pintype "passive"))
      (node (ref "T19") (pin "0") (pintype "passive"))
      (node (ref "U4") (pin "9") (pinfunction "OUT-(C)_9") (pintype "passive"))
    )
    (net (code "68") (name "Net-(U4-S{slash}R+(A,B))") (class "Default")
      (node (ref "C15") (pin "1") (pinfunction "1_1") (pintype "passive"))
      (node (ref "U4") (pin "3") (pinfunction "S/R+(A,B)_3") (pintype "passive"))
      (node (ref "U4") (pin "6") (pinfunction "S/R+(C)_6") (pintype "passive"))
    )
    (net (code "69") (name "Vbat") (class "Default")
      (node (ref "C2") (pin "1") (pinfunction "1_1") (pintype "passive"))
      (node (ref "C3") (pin "1") (pinfunction "1_1") (pintype "passive"))
      (node (ref "P1") (pin "13") (pinfunction "13_13") (pintype "passive"))
      (node (ref "P2") (pin "14") (pinfunction "14_14") (pintype "passive"))
      (node (ref "R9") (pin "1") (pinfunction "1_1") (pintype "passive"))
      (node (ref "T1") (pin "0") (pintype "passive"))
      (node (ref "T4") (pin "0") (pintype "passive"))
      (node (ref "U1") (pin "1") (pinfunction "VIN_1") (pintype "power_in"))
      (node (ref "U1") (pin "2") (pinfunction "VIN_2") (pintype "power_in"))
    )
    (net (code "70") (name "unconnected-(P1-Pad9)") (class "Default")
      (node (ref "P1") (pin "9") (pinfunction "9_9") (pintype "passive"))
    )
    (net (code "71") (name "unconnected-(P1-Pad11)") (class "Default")
      (node (ref "P1") (pin "11") (pinfunction "11_11") (pintype "passive"))
    )
    (net (code "72") (name "unconnected-(P2-Pad12)") (class "Default")
      (node (ref "P2") (pin "12") (pinfunction "12_12") (pintype "passive"))
    )
    (net (code "73") (name "unconnected-(U1-EN-Pad12)") (class "Default")
      (node (ref "U1") (pin "12") (pinfunction "EN_12") (pintype "input"))
    )
    (net (code "74") (name "unconnected-(U1-NC-Pad8)") (class "Default")
      (node (ref "U1") (pin "8") (pinfunction "NC_8") (pintype "passive"))
    )
    (net (code "75") (name "unconnected-(U2-CANRXA{slash}GPIO30-Pad33)") (class "Default")
      (node (ref "U2") (pin "33") (pinfunction "CANRXA/GPIO30_33") (pintype "passive"))
    )
    (net (code "76") (name "unconnected-(U2-CANTXA{slash}GPIO31-Pad32)") (class "Default")
      (node (ref "U2") (pin "32") (pinfunction "CANTXA/GPIO31_32") (pintype "passive"))
    )
    (net (code "77") (name "unconnected-(U2-COMP1OUT{slash}GPIO42-Pad5)") (class "Default")
      (node (ref "U2") (pin "5") (pinfunction "COMP1OUT/GPIO42_5") (pintype "passive"))
    )
    (net (code "78") (name "unconnected-(U2-COMP2OUT{slash}GPIO43-Pad6)") (class "Default")
      (node (ref "U2") (pin "6") (pinfunction "COMP2OUT/GPIO43_6") (pintype "passive"))
    )
    (net (code "79") (name "unconnected-(U2-EPWM1A{slash}GPIO0-Pad69)") (class "Default")
      (node (ref "U2") (pin "69") (pinfunction "EPWM1A/GPIO0_69") (pintype "passive"))
    )
    (net (code "80") (name "unconnected-(U2-EPWM2A{slash}GPIO2-Pad67)") (class "Default")
      (node (ref "U2") (pin "67") (pinfunction "EPWM2A/GPIO2_67") (pintype "passive"))
    )
    (net (code "81") (name "unconnected-(U2-EPWM3A{slash}GPIO4-Pad63)") (class "Default")
      (node (ref "U2") (pin "63") (pinfunction "EPWM3A/GPIO4_63") (pintype "passive"))
    )
    (net (code "82") (name "unconnected-(U2-EPWM7A{slash}GPIO40-Pad64)") (class "Default")
      (node (ref "U2") (pin "64") (pinfunction "EPWM7A/GPIO40_64") (pintype "passive"))
    )
    (net (code "83") (name "unconnected-(U2-EPWM7B{slash}GPIO41-Pad48)") (class "Default")
      (node (ref "U2") (pin "48") (pinfunction "EPWM7B/GPIO41_48") (pintype "passive"))
    )
    (net (code "84") (name "unconnected-(U2-EPWMSYNCI{slash}EPWMSYNCO{slash}EPWM4A{slash}GPIO6-Pad50)") (class "Default")
      (node (ref "U2") (pin "50") (pinfunction "EPWMSYNCI/EPWMSYNCO/EPWM4A/GPIO6_50") (pintype "passive"))
    )
    (net (code "85") (name "unconnected-(U2-GPIO39-Pad56)") (class "Default")
      (node (ref "U2") (pin "56") (pinfunction "GPIO39_56") (pintype "passive"))
    )
    (net (code "86") (name "unconnected-(U2-GPIO44-Pad45)") (class "Default")
      (node (ref "U2") (pin "45") (pinfunction "GPIO44_45") (pintype "passive"))
    )
    (net (code "87") (name "unconnected-(U2-LINRXA{slash}EPWM6B{slash}GPIO11-Pad61)") (class "Default")
      (node (ref "U2") (pin "61") (pinfunction "LINRXA/EPWM6B/GPIO11_61") (pintype "passive"))
    )
    (net (code "88") (name "unconnected-(U2-LINRXA{slash}EQEP1I{slash}GPIO23-Pad4)") (class "Default")
      (node (ref "U2") (pin "4") (pinfunction "LINRXA/EQEP1I/GPIO23_4") (pintype "passive"))
    )
    (net (code "89") (name "unconnected-(U2-LINTXA{slash}EPWM5B{slash}GPIO9-Pad39)") (class "Default")
      (node (ref "U2") (pin "39") (pinfunction "LINTXA/EPWM5B/GPIO9_39") (pintype "passive"))
    )
    (net (code "90") (name "unconnected-(U2-LINTXA{slash}EQEP1S{slash}GPIO22-Pad1)") (class "Default")
      (node (ref "U2") (pin "1") (pinfunction "LINTXA/EQEP1S/GPIO22_1") (pintype "passive"))
    )
    (net (code "91") (name "unconnected-(U2-SCIRXDA{slash}EPWM4B{slash}GPIO7-Pad49)") (class "Default")
      (node (ref "U2") (pin "49") (pinfunction "SCIRXDA/EPWM4B/GPIO7_49") (pintype "passive"))
    )
    (net (code "92") (name "unconnected-(U2-SCIRXDA{slash}SDAA{slash}~{TZ2}{slash}GPIO28-Pad40)") (class "Default")
      (node (ref "U2") (pin "40") (pinfunction "SCIRXDA/SDAA/~{TZ2}/GPIO28_40") (pintype "passive"))
    )
    (net (code "93") (name "unconnected-(U2-SCITXDA{slash}SCLA{slash}~{TZ3}{slash}GPIO29-Pad34)") (class "Default")
      (node (ref "U2") (pin "34") (pinfunction "SCITXDA/SCLA/~{TZ3}/GPIO29_34") (pintype "passive"))
    )
    (net (code "94") (name "unconnected-(U2-SPICLKB{slash}GPIO26-Pad37)") (class "Default")
      (node (ref "U2") (pin "37") (pinfunction "SPICLKB/GPIO26_37") (pintype "passive"))
    )
    (net (code "95") (name "unconnected-(U2-SPISIMOA{slash}ECAP1{slash}EPWM3B{slash}GPIO5-Pad62)") (class "Default")
      (node (ref "U2") (pin "62") (pinfunction "SPISIMOA/ECAP1/EPWM3B/GPIO5_62") (pintype "passive"))
    )
    (net (code "96") (name "unconnected-(U2-SPISIMOA{slash}~{TZ2}{slash}GPIO16-Pad46)") (class "Default")
      (node (ref "U2") (pin "46") (pinfunction "SPISIMOA/~{TZ2}/GPIO16_46") (pintype "passive"))
    )
    (net (code "97") (name "unconnected-(U2-SPISIMOB{slash}SCITXDA{slash}~{TZ1}{slash}GPIO12-Pad47)") (class "Default")
      (node (ref "U2") (pin "47") (pinfunction "SPISIMOB/SCITXDA/~{TZ1}/GPIO12_47") (pintype "passive"))
    )
    (net (code "98") (name "unconnected-(U2-SPISOMIA{slash}COMP2OUT{slash}EPWM2B{slash}GPIO3-Pad66)") (class "Default")
      (node (ref "U2") (pin "66") (pinfunction "SPISOMIA/COMP2OUT/EPWM2B/GPIO3_66") (pintype "passive"))
    )
    (net (code "99") (name "unconnected-(U2-SPISOMIB{slash}GPIO25-Pad44)") (class "Default")
      (node (ref "U2") (pin "44") (pinfunction "SPISOMIB/GPIO25_44") (pintype "passive"))
    )
    (net (code "100") (name "unconnected-(U2-TEST2-Pad38)") (class "Default")
      (node (ref "U2") (pin "38") (pinfunction "TEST2_38") (pintype "passive"))
    )
    (net (code "101") (name "unconnected-(U2-VREFHI-Pad19)") (class "Default")
      (node (ref "U2") (pin "19") (pinfunction "VREFHI_19") (pintype "passive"))
    )
    (net (code "102") (name "unconnected-(U2-~{ADCSOCAO}{slash}EPWM5A{slash}GPIO8-Pad43)") (class "Default")
      (node (ref "U2") (pin "43") (pinfunction "~{ADCSOCAO}/EPWM5A/GPIO8_43") (pintype "passive"))
    )
    (net (code "103") (name "unconnected-(U2-~{ADCSOCAO}{slash}SDAA{slash}EPWMSYNC{slash}GPIO32-Pad2)") (class "Default")
      (node (ref "U2") (pin "2") (pinfunction "~{ADCSOCAO}/SDAA/EPWMSYNC/GPIO32_2") (pintype "passive"))
    )
    (net (code "104") (name "unconnected-(U2-~{ADCSOCBO}{slash}EPWM6A{slash}GPIO10-Pad65)") (class "Default")
      (node (ref "U2") (pin "65") (pinfunction "~{ADCSOCBO}/EPWM6A/GPIO10_65") (pintype "passive"))
    )
    (net (code "105") (name "unconnected-(U2-~{ADCSOCBO}{slash}SCLA{slash}EPWMSYNCO{slash}GPIO33-Pad3)") (class "Default")
      (node (ref "U2") (pin "3") (pinfunction "~{ADCSOCBO}/SCLA/EPWMSYNCO/GPIO33_3") (pintype "passive"))
    )
    (net (code "106") (name "unconnected-(U2-~{SPISTEA}{slash}LINRXA{slash}ECAP1{slash}XCLKIN{slash}GPIO19-Pad55)") (class "Default")
      (node (ref "U2") (pin "55") (pinfunction "~{SPISTEA}/LINRXA/ECAP1/XCLKIN/GPIO19_55") (pintype "passive"))
    )
    (net (code "107") (name "unconnected-(U2-~{SPISTEB}{slash}GPIO27-Pad31)") (class "Default")
      (node (ref "U2") (pin "31") (pinfunction "~{SPISTEB}/GPIO27_31") (pintype "passive"))
    )
    (net (code "108") (name "unconnected-(U2-~{XRS}-Pad9)") (class "Default")
      (node (ref "U2") (pin "9") (pinfunction "~{XRS}_9") (pintype "passive"))
    )
    (net (code "109") (name "unconnected-(U3A-V+-Pad4)") (class "Default")
      (node (ref "U3") (pin "4") (pinfunction "V+_4") (pintype "power_in"))
    )
    (net (code "110") (name "unconnected-(U3A-V--Pad11)") (class "Default")
      (node (ref "U3") (pin "11") (pinfunction "V-_11") (pintype "power_in"))
    )
    (net (code "111") (name "unconnected-(U3B-V+-Pad4)") (class "Default")
      (node (ref "U3") (pin "4") (pinfunction "V+_4") (pintype "power_in"))
    )
    (net (code "112") (name "unconnected-(U3B-V--Pad11)") (class "Default")
      (node (ref "U3") (pin "11") (pinfunction "V-_11") (pintype "power_in"))
    )
    (net (code "113") (name "unconnected-(U3C-V+-Pad4)") (class "Default")
      (node (ref "U3") (pin "4") (pinfunction "V+_4") (pintype "power_in"))
    )
    (net (code "114") (name "unconnected-(U3C-V--Pad11)") (class "Default")
      (node (ref "U3") (pin "11") (pinfunction "V-_11") (pintype "power_in"))
    )
    (net (code "115") (name "unconnected-(U4-OFF+(A,B,C)-Pad15)") (class "Default")
      (node (ref "U4") (pin "15") (pinfunction "OFF+(A,B,C)_15") (pintype "passive"))
    )
    (net (code "116") (name "unconnected-(U4-OFF-(A,B)-Pad2)") (class "Default")
      (node (ref "U4") (pin "2") (pinfunction "OFF-(A,B)_2") (pintype "passive"))
    )
    (net (code "117") (name "unconnected-(U4-OFF-(C)-Pad7)") (class "Default")
      (node (ref "U4") (pin "7") (pinfunction "OFF-(C)_7") (pintype "passive"))
    )
    (net (code "118") (name "unconnected-(Y1-FLT-Pad2)") (class "Default")
      (node (ref "Y1") (pin "2") (pinfunction "FLT_2") (pintype "passive"))
    )
  )
)
